# simple-differential-power-supply-rev1.net
KiCad netlist of a schematic drawn in EAGLE
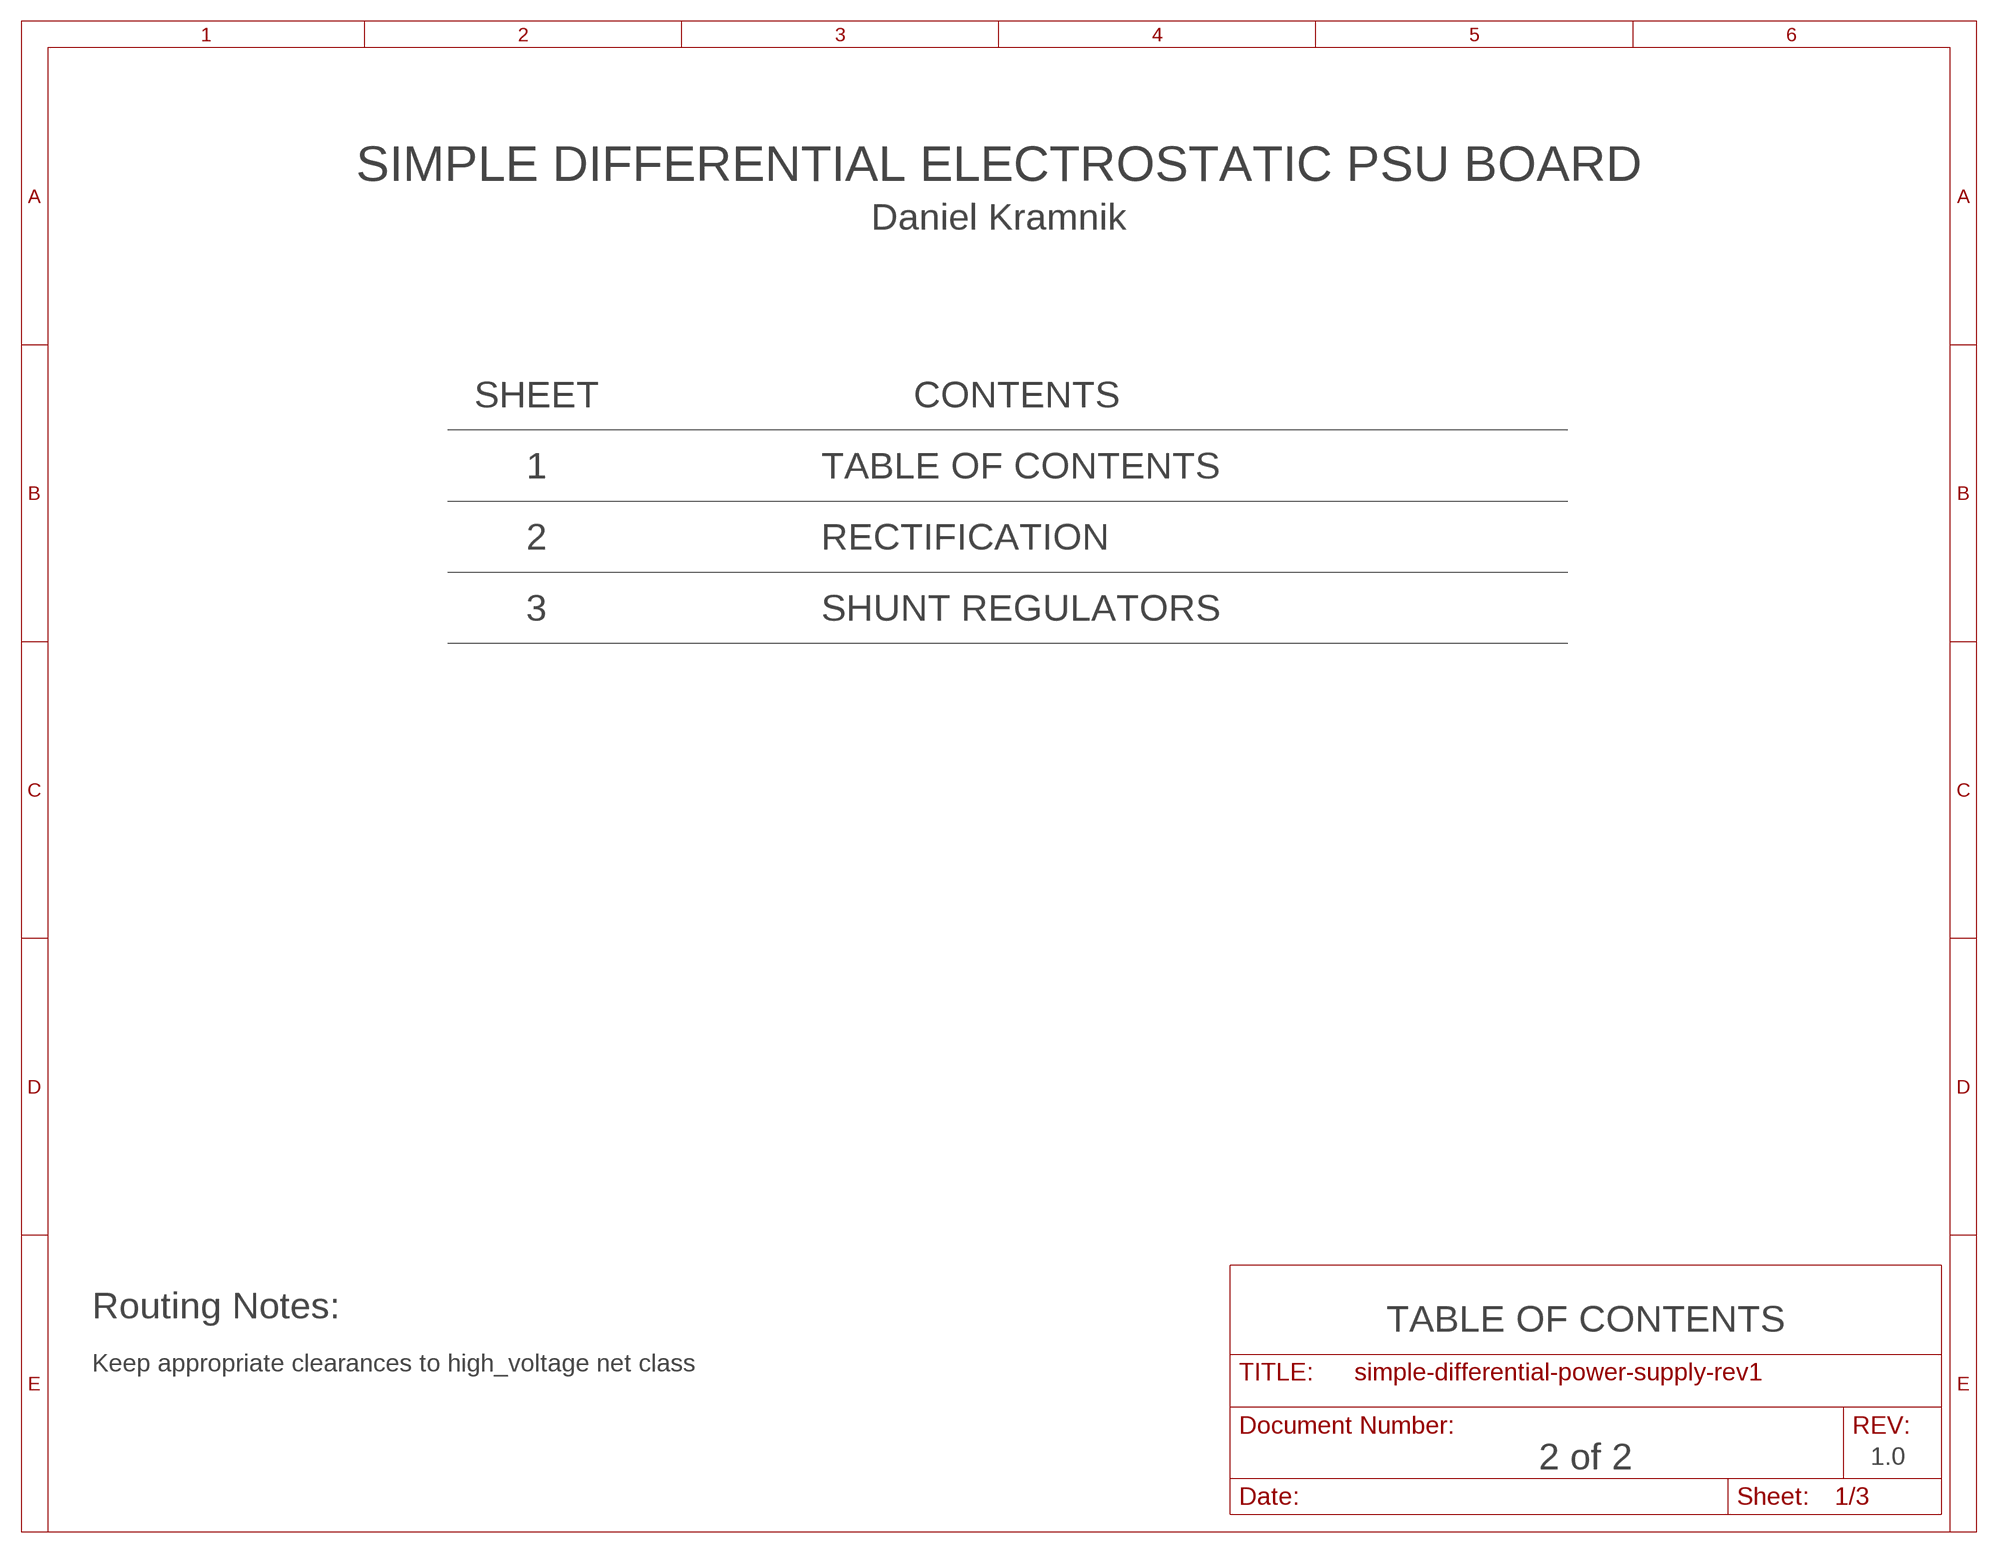
[diagram p0: schematic, sheet 1]
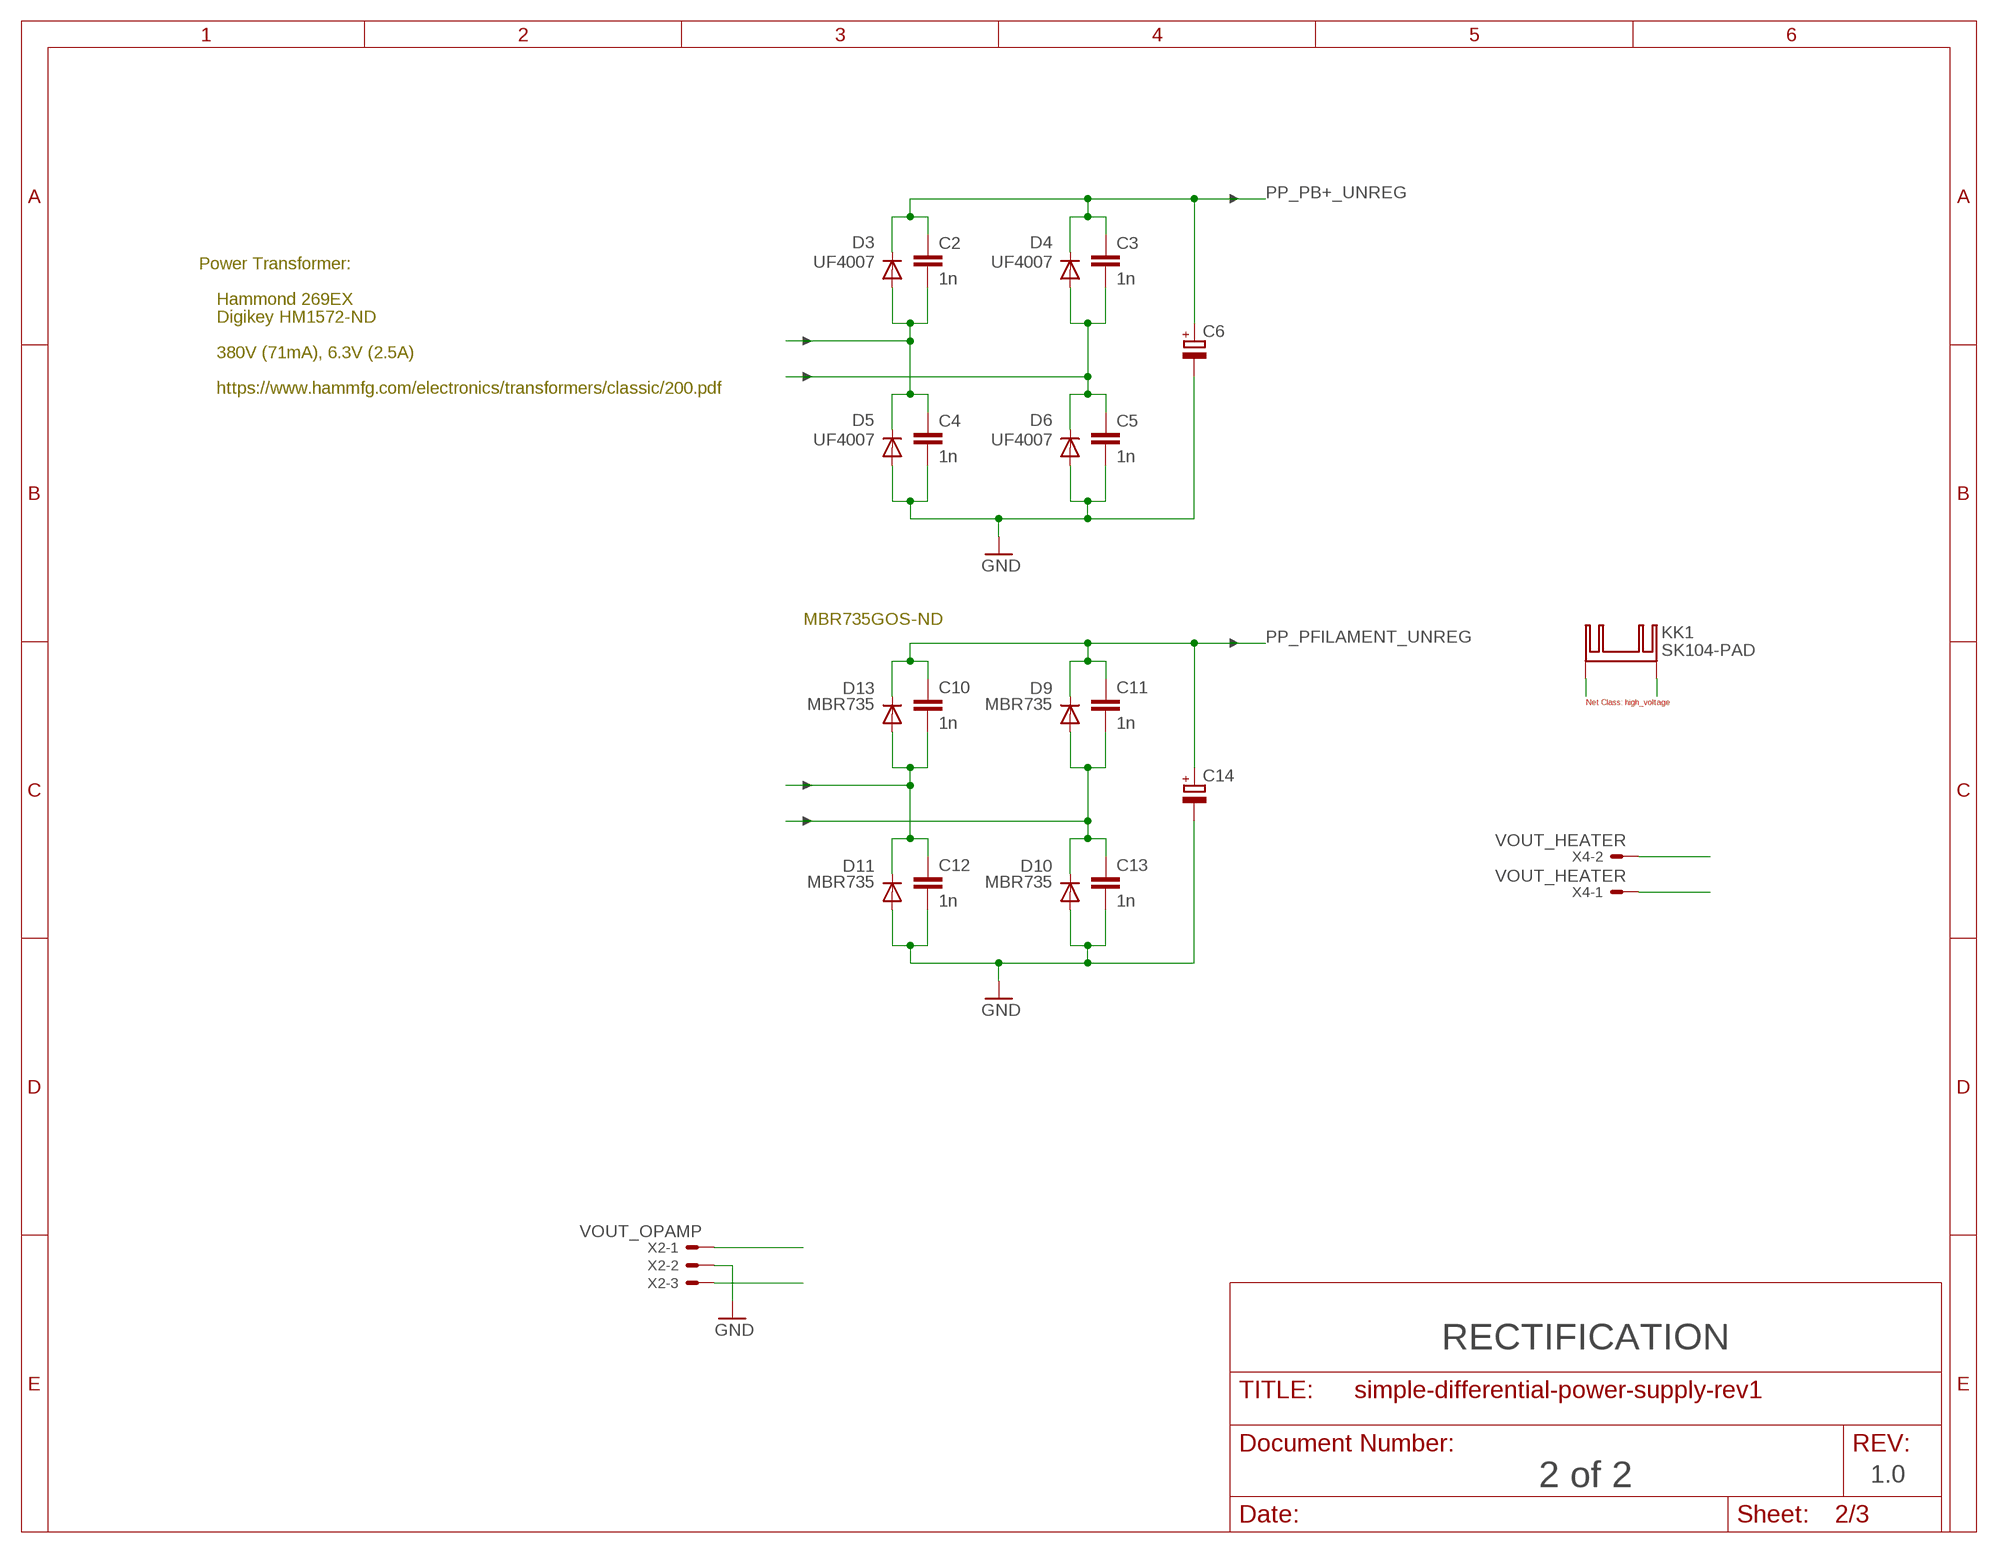
[diagram p1: schematic, sheet 2]
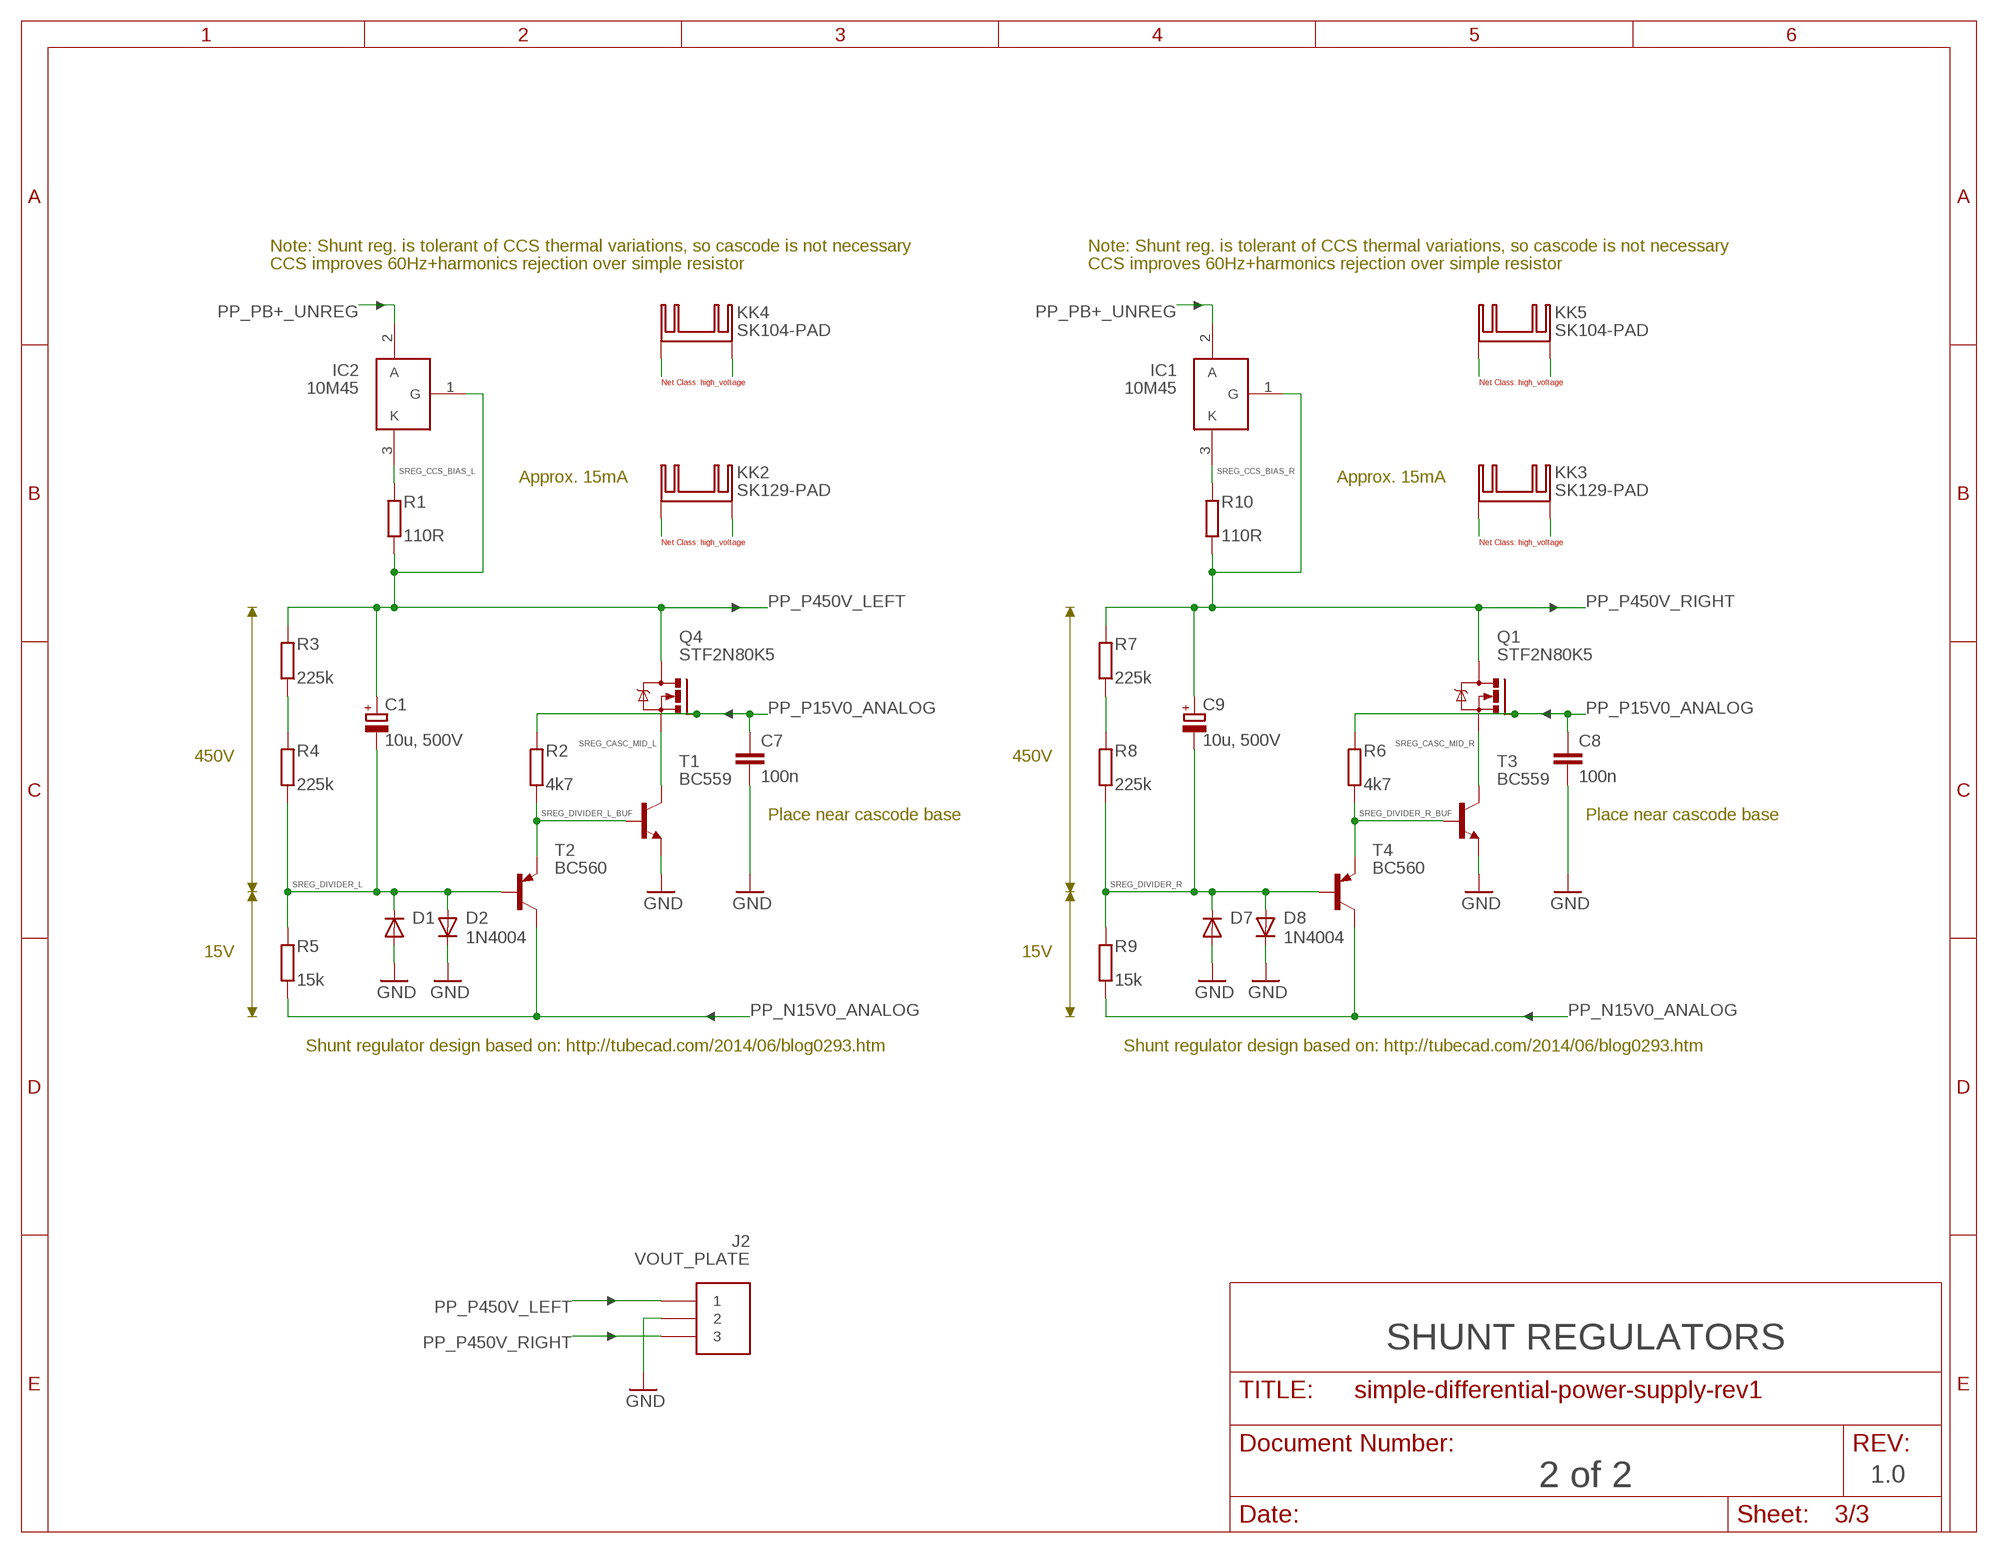
[diagram p2: schematic, sheet 3]

(export (version "E")
  (design (tool "Eeschema 10.0.6"))
  (components
    (comp (ref "C2")
      (value "1n")
      (footprint "eagle-import:C225-087X268")
      (libsource (lib "eagle-import") (part "C-EU225-087X268"))
    )
    (comp (ref "C3")
      (value "1n")
      (footprint "eagle-import:C225-087X268")
      (libsource (lib "eagle-import") (part "C-EU225-087X268"))
    )
    (comp (ref "C4")
      (value "1n")
      (footprint "eagle-import:C225-087X268")
      (libsource (lib "eagle-import") (part "C-EU225-087X268"))
    )
    (comp (ref "C5")
      (value "1n")
      (footprint "eagle-import:C225-087X268")
      (libsource (lib "eagle-import") (part "C-EU225-087X268"))
    )
    (comp (ref "C6")
      (value "CPOL-EUE10-25")
      (footprint "eagle-import:EB25D")
      (libsource (lib "eagle-import") (part "CPOL-EUE10-25"))
    )
    (comp (ref "C10")
      (value "1n")
      (footprint "eagle-import:C225-087X268")
      (libsource (lib "eagle-import") (part "C-EU225-087X268"))
    )
    (comp (ref "C11")
      (value "1n")
      (footprint "eagle-import:C225-087X268")
      (libsource (lib "eagle-import") (part "C-EU225-087X268"))
    )
    (comp (ref "C12")
      (value "1n")
      (footprint "eagle-import:C225-087X268")
      (libsource (lib "eagle-import") (part "C-EU225-087X268"))
    )
    (comp (ref "C13")
      (value "1n")
      (footprint "eagle-import:C225-087X268")
      (libsource (lib "eagle-import") (part "C-EU225-087X268"))
    )
    (comp (ref "C14")
      (value "CPOL-EUE10-25")
      (footprint "eagle-import:EB25D")
      (libsource (lib "eagle-import") (part "CPOL-EUE10-25"))
    )
    (comp (ref "D3")
      (value "UF4007")
      (footprint "eagle-import:DO41-10")
      (libsource (lib "eagle-import") (part "1N4004"))
    )
    (comp (ref "D4")
      (value "UF4007")
      (footprint "eagle-import:DO41-10")
      (libsource (lib "eagle-import") (part "1N4004"))
    )
    (comp (ref "D5")
      (value "UF4007")
      (footprint "eagle-import:DO41-10")
      (libsource (lib "eagle-import") (part "1N4004"))
    )
    (comp (ref "D6")
      (value "UF4007")
      (footprint "eagle-import:DO41-10")
      (libsource (lib "eagle-import") (part "1N4004"))
    )
    (comp (ref "D9")
      (value "MBR735")
      (footprint "eagle-import:TO220ACS")
      (libsource (lib "eagle-import") (part "DIODE-TO220V"))
    )
    (comp (ref "D10")
      (value "MBR735")
      (footprint "eagle-import:TO220ACS")
      (libsource (lib "eagle-import") (part "DIODE-TO220V"))
    )
    (comp (ref "D11")
      (value "MBR735")
      (footprint "eagle-import:TO220ACS")
      (libsource (lib "eagle-import") (part "DIODE-TO220V"))
    )
    (comp (ref "D13")
      (value "MBR735")
      (footprint "eagle-import:TO220ACS")
      (libsource (lib "eagle-import") (part "DIODE-TO220V"))
    )
    (comp (ref "KK1")
      (value "SK104-PAD")
      (footprint "eagle-import:SK104-PAD")
      (libsource (lib "eagle-import") (part "SK104-PAD"))
    )
    (comp (ref "X2")
      (value "VOUT_OPAMP")
      (footprint "eagle-import:KK-156-3")
      (libsource (lib "eagle-import") (part "KK-156-3"))
    )
    (comp (ref "X4")
      (value "VOUT_HEATER")
      (footprint "eagle-import:KK-156-2")
      (libsource (lib "eagle-import") (part "KK-156-2"))
    )
    (comp (ref "C1")
      (value "10u, 500V")
      (footprint "eagle-import:EB25D")
      (libsource (lib "eagle-import") (part "CPOL-EUE10-25"))
    )
    (comp (ref "C7")
      (value "100n")
      (footprint "eagle-import:C050-025X075")
      (libsource (lib "eagle-import") (part "C-EU050-025X075"))
    )
    (comp (ref "C8")
      (value "100n")
      (footprint "eagle-import:C050-025X075")
      (libsource (lib "eagle-import") (part "C-EU050-025X075"))
    )
    (comp (ref "C9")
      (value "10u, 500V")
      (footprint "eagle-import:EB25D")
      (libsource (lib "eagle-import") (part "CPOL-EUE10-25"))
    )
    (comp (ref "D1")
      (value "1N4004")
      (footprint "eagle-import:DO41-10")
      (libsource (lib "eagle-import") (part "1N4004"))
    )
    (comp (ref "D2")
      (value "1N4004")
      (footprint "eagle-import:DO41-10")
      (libsource (lib "eagle-import") (part "1N4004"))
    )
    (comp (ref "D7")
      (value "1N4004")
      (footprint "eagle-import:DO41-10")
      (libsource (lib "eagle-import") (part "1N4004"))
    )
    (comp (ref "D8")
      (value "1N4004")
      (footprint "eagle-import:DO41-10")
      (libsource (lib "eagle-import") (part "1N4004"))
    )
    (comp (ref "IC1")
      (value "10M45")
      (footprint "eagle-import:TO220V")
      (libsource (lib "eagle-import") (part "10M45V"))
    )
    (comp (ref "IC2")
      (value "10M45")
      (footprint "eagle-import:TO220V")
      (libsource (lib "eagle-import") (part "10M45V"))
    )
    (comp (ref "J2")
      (value "VOUT_PLATE")
      (footprint "eagle-import:CONN_MOLEX_3PIN_MINI-FIT_JR")
      (libsource (lib "eagle-import") (part "CONN_MOLEX_3PIN_MINI-FIT_JR"))
    )
    (comp (ref "KK2")
      (value "SK129-PAD")
      (footprint "eagle-import:SK129")
      (libsource (lib "eagle-import") (part "SK129-PAD"))
    )
    (comp (ref "KK3")
      (value "SK129-PAD")
      (footprint "eagle-import:SK129")
      (libsource (lib "eagle-import") (part "SK129-PAD"))
    )
    (comp (ref "KK4")
      (value "SK104-PAD")
      (footprint "eagle-import:SK104-PAD")
      (libsource (lib "eagle-import") (part "SK104-PAD"))
    )
    (comp (ref "KK5")
      (value "SK104-PAD")
      (footprint "eagle-import:SK104-PAD")
      (libsource (lib "eagle-import") (part "SK104-PAD"))
    )
    (comp (ref "Q1")
      (value "STF2N80K5")
      (footprint "eagle-import:TO220BV")
      (libsource (lib "eagle-import") (part "IRF540"))
    )
    (comp (ref "Q4")
      (value "STF2N80K5")
      (footprint "eagle-import:TO220BV")
      (libsource (lib "eagle-import") (part "IRF540"))
    )
    (comp (ref "R1")
      (value "110R")
      (footprint "eagle-import:0309_10")
      (libsource (lib "eagle-import") (part "R-EU_0309/10"))
    )
    (comp (ref "R2")
      (value "4k7")
      (footprint "eagle-import:0309_10")
      (libsource (lib "eagle-import") (part "R-EU_0309/10"))
    )
    (comp (ref "R3")
      (value "225k")
      (footprint "eagle-import:0309_10")
      (libsource (lib "eagle-import") (part "R-EU_0309/10"))
    )
    (comp (ref "R4")
      (value "225k")
      (footprint "eagle-import:0309_10")
      (libsource (lib "eagle-import") (part "R-EU_0309/10"))
    )
    (comp (ref "R5")
      (value "15k")
      (footprint "eagle-import:0309_10")
      (libsource (lib "eagle-import") (part "R-EU_0309/10"))
    )
    (comp (ref "R6")
      (value "4k7")
      (footprint "eagle-import:0309_10")
      (libsource (lib "eagle-import") (part "R-EU_0309/10"))
    )
    (comp (ref "R7")
      (value "225k")
      (footprint "eagle-import:0309_10")
      (libsource (lib "eagle-import") (part "R-EU_0309/10"))
    )
    (comp (ref "R8")
      (value "225k")
      (footprint "eagle-import:0309_10")
      (libsource (lib "eagle-import") (part "R-EU_0309/10"))
    )
    (comp (ref "R9")
      (value "15k")
      (footprint "eagle-import:0309_10")
      (libsource (lib "eagle-import") (part "R-EU_0309/10"))
    )
    (comp (ref "R10")
      (value "110R")
      (footprint "eagle-import:0309_10")
      (libsource (lib "eagle-import") (part "R-EU_0309/10"))
    )
    (comp (ref "T1")
      (value "BC559")
      (footprint "eagle-import:TO92-EBC")
      (libsource (lib "eagle-import") (part "-NPN-TO92-EBC2N5088"))
    )
    (comp (ref "T2")
      (value "BC560")
      (footprint "eagle-import:TO92-EBC")
      (libsource (lib "eagle-import") (part "-PNP-TO92-EBC2N5087"))
    )
    (comp (ref "T3")
      (value "BC559")
      (footprint "eagle-import:TO92-EBC")
      (libsource (lib "eagle-import") (part "-NPN-TO92-EBC2N5088"))
    )
    (comp (ref "T4")
      (value "BC560")
      (footprint "eagle-import:TO92-EBC")
      (libsource (lib "eagle-import") (part "-PNP-TO92-EBC2N5087"))
    )
  )
  (nets
    (net (code "1") (name "GND") (class "Default")
      (node (ref "C12") (pin "2") (pinfunction "2_2") (pintype "passive"))
      (node (ref "C13") (pin "2") (pinfunction "2_2") (pintype "passive"))
      (node (ref "C14") (pin "-") (pinfunction "-_-") (pintype "passive"))
      (node (ref "C4") (pin "2") (pinfunction "2_2") (pintype "passive"))
      (node (ref "C5") (pin "2") (pinfunction "2_2") (pintype "passive"))
      (node (ref "C6") (pin "-") (pinfunction "-_-") (pintype "passive"))
      (node (ref "C7") (pin "2") (pinfunction "2_2") (pintype "passive"))
      (node (ref "C8") (pin "2") (pinfunction "2_2") (pintype "passive"))
      (node (ref "D1") (pin "A") (pinfunction "A_A") (pintype "passive"))
      (node (ref "D10") (pin "A") (pinfunction "A_A") (pintype "passive"))
      (node (ref "D11") (pin "A") (pinfunction "A_A") (pintype "passive"))
      (node (ref "D2") (pin "C") (pinfunction "C_C") (pintype "passive"))
      (node (ref "D5") (pin "A") (pinfunction "A_A") (pintype "passive"))
      (node (ref "D6") (pin "A") (pinfunction "A_A") (pintype "passive"))
      (node (ref "D7") (pin "A") (pinfunction "A_A") (pintype "passive"))
      (node (ref "D8") (pin "C") (pinfunction "C_C") (pintype "passive"))
      (node (ref "J2") (pin "2") (pinfunction "2_2") (pintype "bidirectional"))
      (node (ref "T1") (pin "E") (pinfunction "E_E") (pintype "passive"))
      (node (ref "T3") (pin "E") (pinfunction "E_E") (pintype "passive"))
      (node (ref "X2") (pin "2") (pinfunction "S_2") (pintype "passive"))
    )
    (net (code "2") (name "Net-(C2-Pad2)") (class "Default")
      (node (ref "C2") (pin "2") (pinfunction "2_2") (pintype "passive"))
      (node (ref "C4") (pin "1") (pinfunction "1_1") (pintype "passive"))
      (node (ref "D3") (pin "A") (pinfunction "A_A") (pintype "passive"))
      (node (ref "D5") (pin "C") (pinfunction "C_C") (pintype "passive"))
    )
    (net (code "3") (name "Net-(C3-Pad2)") (class "Default")
      (node (ref "C3") (pin "2") (pinfunction "2_2") (pintype "passive"))
      (node (ref "C5") (pin "1") (pinfunction "1_1") (pintype "passive"))
      (node (ref "D4") (pin "A") (pinfunction "A_A") (pintype "passive"))
      (node (ref "D6") (pin "C") (pinfunction "C_C") (pintype "passive"))
    )
    (net (code "4") (name "Net-(C10-Pad2)") (class "Default")
      (node (ref "C10") (pin "2") (pinfunction "2_2") (pintype "passive"))
      (node (ref "C12") (pin "1") (pinfunction "1_1") (pintype "passive"))
      (node (ref "D11") (pin "C") (pinfunction "C_C") (pintype "passive"))
      (node (ref "D13") (pin "A") (pinfunction "A_A") (pintype "passive"))
    )
    (net (code "5") (name "Net-(C11-Pad2)") (class "Default")
      (node (ref "C11") (pin "2") (pinfunction "2_2") (pintype "passive"))
      (node (ref "C13") (pin "1") (pinfunction "1_1") (pintype "passive"))
      (node (ref "D10") (pin "C") (pinfunction "C_C") (pintype "passive"))
      (node (ref "D9") (pin "A") (pinfunction "A_A") (pintype "passive"))
    )
    (net (code "6") (name "Net-(R3-Pad1)") (class "Default")
      (node (ref "R3") (pin "1") (pinfunction "1_1") (pintype "passive"))
      (node (ref "R4") (pin "2") (pinfunction "2_2") (pintype "passive"))
    )
    (net (code "7") (name "Net-(R7-Pad1)") (class "Default")
      (node (ref "R7") (pin "1") (pinfunction "1_1") (pintype "passive"))
      (node (ref "R8") (pin "2") (pinfunction "2_2") (pintype "passive"))
    )
    (net (code "8") (name "PP_N15V0_ANALOG") (class "Default")
      (node (ref "R5") (pin "1") (pinfunction "1_1") (pintype "passive"))
      (node (ref "R9") (pin "1") (pinfunction "1_1") (pintype "passive"))
      (node (ref "T2") (pin "C") (pinfunction "C_C") (pintype "passive"))
      (node (ref "T4") (pin "C") (pinfunction "C_C") (pintype "passive"))
    )
    (net (code "9") (name "PP_P15V0_ANALOG") (class "Default")
      (node (ref "C7") (pin "1") (pinfunction "1_1") (pintype "passive"))
      (node (ref "C8") (pin "1") (pinfunction "1_1") (pintype "passive"))
      (node (ref "Q1") (pin "G") (pinfunction "G_G") (pintype "passive"))
      (node (ref "Q4") (pin "G") (pinfunction "G_G") (pintype "passive"))
      (node (ref "R2") (pin "2") (pinfunction "2_2") (pintype "passive"))
      (node (ref "R6") (pin "2") (pinfunction "2_2") (pintype "passive"))
    )
    (net (code "10") (name "PP_P450V_LEFT") (class "Default")
      (node (ref "C1") (pin "+") (pinfunction "+_+") (pintype "passive"))
      (node (ref "IC2") (pin "1") (pinfunction "G_1") (pintype "bidirectional"))
      (node (ref "J2") (pin "1") (pinfunction "1_1") (pintype "bidirectional"))
      (node (ref "Q4") (pin "D") (pinfunction "D_D") (pintype "passive"))
      (node (ref "R1") (pin "1") (pinfunction "1_1") (pintype "passive"))
      (node (ref "R3") (pin "2") (pinfunction "2_2") (pintype "passive"))
    )
    (net (code "11") (name "PP_P450V_RIGHT") (class "Default")
      (node (ref "C9") (pin "+") (pinfunction "+_+") (pintype "passive"))
      (node (ref "IC1") (pin "1") (pinfunction "G_1") (pintype "bidirectional"))
      (node (ref "J2") (pin "3") (pinfunction "3_3") (pintype "bidirectional"))
      (node (ref "Q1") (pin "D") (pinfunction "D_D") (pintype "passive"))
      (node (ref "R10") (pin "1") (pinfunction "1_1") (pintype "passive"))
      (node (ref "R7") (pin "2") (pinfunction "2_2") (pintype "passive"))
    )
    (net (code "12") (name "PP_PB+_UNREG") (class "Default")
      (node (ref "C2") (pin "1") (pinfunction "1_1") (pintype "passive"))
      (node (ref "C3") (pin "1") (pinfunction "1_1") (pintype "passive"))
      (node (ref "C6") (pin "+") (pinfunction "+_+") (pintype "passive"))
      (node (ref "D3") (pin "C") (pinfunction "C_C") (pintype "passive"))
      (node (ref "D4") (pin "C") (pinfunction "C_C") (pintype "passive"))
      (node (ref "IC1") (pin "2") (pinfunction "A_2") (pintype "bidirectional"))
      (node (ref "IC2") (pin "2") (pinfunction "A_2") (pintype "bidirectional"))
    )
    (net (code "13") (name "PP_PFILAMENT_UNREG") (class "Default")
      (node (ref "C10") (pin "1") (pinfunction "1_1") (pintype "passive"))
      (node (ref "C11") (pin "1") (pinfunction "1_1") (pintype "passive"))
      (node (ref "C14") (pin "+") (pinfunction "+_+") (pintype "passive"))
      (node (ref "D13") (pin "C") (pinfunction "C_C") (pintype "passive"))
      (node (ref "D9") (pin "C") (pinfunction "C_C") (pintype "passive"))
    )
    (net (code "14") (name "SREG_CASC_MID_L") (class "Default")
      (node (ref "Q4") (pin "S") (pinfunction "S_S") (pintype "passive"))
      (node (ref "T1") (pin "C") (pinfunction "C_C") (pintype "passive"))
    )
    (net (code "15") (name "SREG_CASC_MID_R") (class "Default")
      (node (ref "Q1") (pin "S") (pinfunction "S_S") (pintype "passive"))
      (node (ref "T3") (pin "C") (pinfunction "C_C") (pintype "passive"))
    )
    (net (code "16") (name "SREG_CCS_BIAS_L") (class "Default")
      (node (ref "IC2") (pin "3") (pinfunction "K_3") (pintype "bidirectional"))
      (node (ref "R1") (pin "2") (pinfunction "2_2") (pintype "passive"))
    )
    (net (code "17") (name "SREG_CCS_BIAS_R") (class "Default")
      (node (ref "IC1") (pin "3") (pinfunction "K_3") (pintype "bidirectional"))
      (node (ref "R10") (pin "2") (pinfunction "2_2") (pintype "passive"))
    )
    (net (code "18") (name "SREG_DIVIDER_L") (class "Default")
      (node (ref "C1") (pin "-") (pinfunction "-_-") (pintype "passive"))
      (node (ref "D1") (pin "C") (pinfunction "C_C") (pintype "passive"))
      (node (ref "D2") (pin "A") (pinfunction "A_A") (pintype "passive"))
      (node (ref "R4") (pin "1") (pinfunction "1_1") (pintype "passive"))
      (node (ref "R5") (pin "2") (pinfunction "2_2") (pintype "passive"))
      (node (ref "T2") (pin "B") (pinfunction "B_B") (pintype "passive"))
    )
    (net (code "19") (name "SREG_DIVIDER_L_BUF") (class "Default")
      (node (ref "R2") (pin "1") (pinfunction "1_1") (pintype "passive"))
      (node (ref "T1") (pin "B") (pinfunction "B_B") (pintype "passive"))
      (node (ref "T2") (pin "E") (pinfunction "E_E") (pintype "passive"))
    )
    (net (code "20") (name "SREG_DIVIDER_R") (class "Default")
      (node (ref "C9") (pin "-") (pinfunction "-_-") (pintype "passive"))
      (node (ref "D7") (pin "C") (pinfunction "C_C") (pintype "passive"))
      (node (ref "D8") (pin "A") (pinfunction "A_A") (pintype "passive"))
      (node (ref "R8") (pin "1") (pinfunction "1_1") (pintype "passive"))
      (node (ref "R9") (pin "2") (pinfunction "2_2") (pintype "passive"))
      (node (ref "T4") (pin "B") (pinfunction "B_B") (pintype "passive"))
    )
    (net (code "21") (name "SREG_DIVIDER_R_BUF") (class "Default")
      (node (ref "R6") (pin "1") (pinfunction "1_1") (pintype "passive"))
      (node (ref "T3") (pin "B") (pinfunction "B_B") (pintype "passive"))
      (node (ref "T4") (pin "E") (pinfunction "E_E") (pintype "passive"))
    )
    (net (code "22") (name "unconnected-(KK1-K-PadK1)") (class "Default")
      (node (ref "KK1") (pin "K1") (pinfunction "K_K1") (pintype "passive"))
    )
    (net (code "23") (name "unconnected-(KK1-K-PadK2)") (class "Default")
      (node (ref "KK1") (pin "K2") (pinfunction "K_K2") (pintype "passive"))
    )
    (net (code "24") (name "unconnected-(KK2-K-PadA2,5)") (class "Default")
      (node (ref "KK2") (pin "A2,5") (pinfunction "K_A2,5") (pintype "passive"))
    )
    (net (code "25") (name "unconnected-(KK2-K-PadB2,5)") (class "Default")
      (node (ref "KK2") (pin "B2,5") (pinfunction "K_B2,5") (pintype "passive"))
    )
    (net (code "26") (name "unconnected-(KK3-K-PadA2,5)") (class "Default")
      (node (ref "KK3") (pin "A2,5") (pinfunction "K_A2,5") (pintype "passive"))
    )
    (net (code "27") (name "unconnected-(KK3-K-PadB2,5)") (class "Default")
      (node (ref "KK3") (pin "B2,5") (pinfunction "K_B2,5") (pintype "passive"))
    )
    (net (code "28") (name "unconnected-(KK4-K-PadK1)") (class "Default")
      (node (ref "KK4") (pin "K1") (pinfunction "K_K1") (pintype "passive"))
    )
    (net (code "29") (name "unconnected-(KK4-K-PadK2)") (class "Default")
      (node (ref "KK4") (pin "K2") (pinfunction "K_K2") (pintype "passive"))
    )
    (net (code "30") (name "unconnected-(KK5-K-PadK1)") (class "Default")
      (node (ref "KK5") (pin "K1") (pinfunction "K_K1") (pintype "passive"))
    )
    (net (code "31") (name "unconnected-(KK5-K-PadK2)") (class "Default")
      (node (ref "KK5") (pin "K2") (pinfunction "K_K2") (pintype "passive"))
    )
    (net (code "32") (name "unconnected-(X2A-S-Pad1)") (class "Default")
      (node (ref "X2") (pin "1") (pinfunction "S_1") (pintype "passive"))
    )
    (net (code "33") (name "unconnected-(X2C-S-Pad3)") (class "Default")
      (node (ref "X2") (pin "3") (pinfunction "S_3") (pintype "passive"))
    )
    (net (code "34") (name "unconnected-(X4A-S-Pad1)") (class "Default")
      (node (ref "X4") (pin "1") (pinfunction "S_1") (pintype "passive"))
    )
    (net (code "35") (name "unconnected-(X4B-S-Pad2)") (class "Default")
      (node (ref "X4") (pin "2") (pinfunction "S_2") (pintype "passive"))
    )
  )
)
